# bitfury_m-board-v2_3.net
KiCad netlist of a schematic drawn in EAGLE
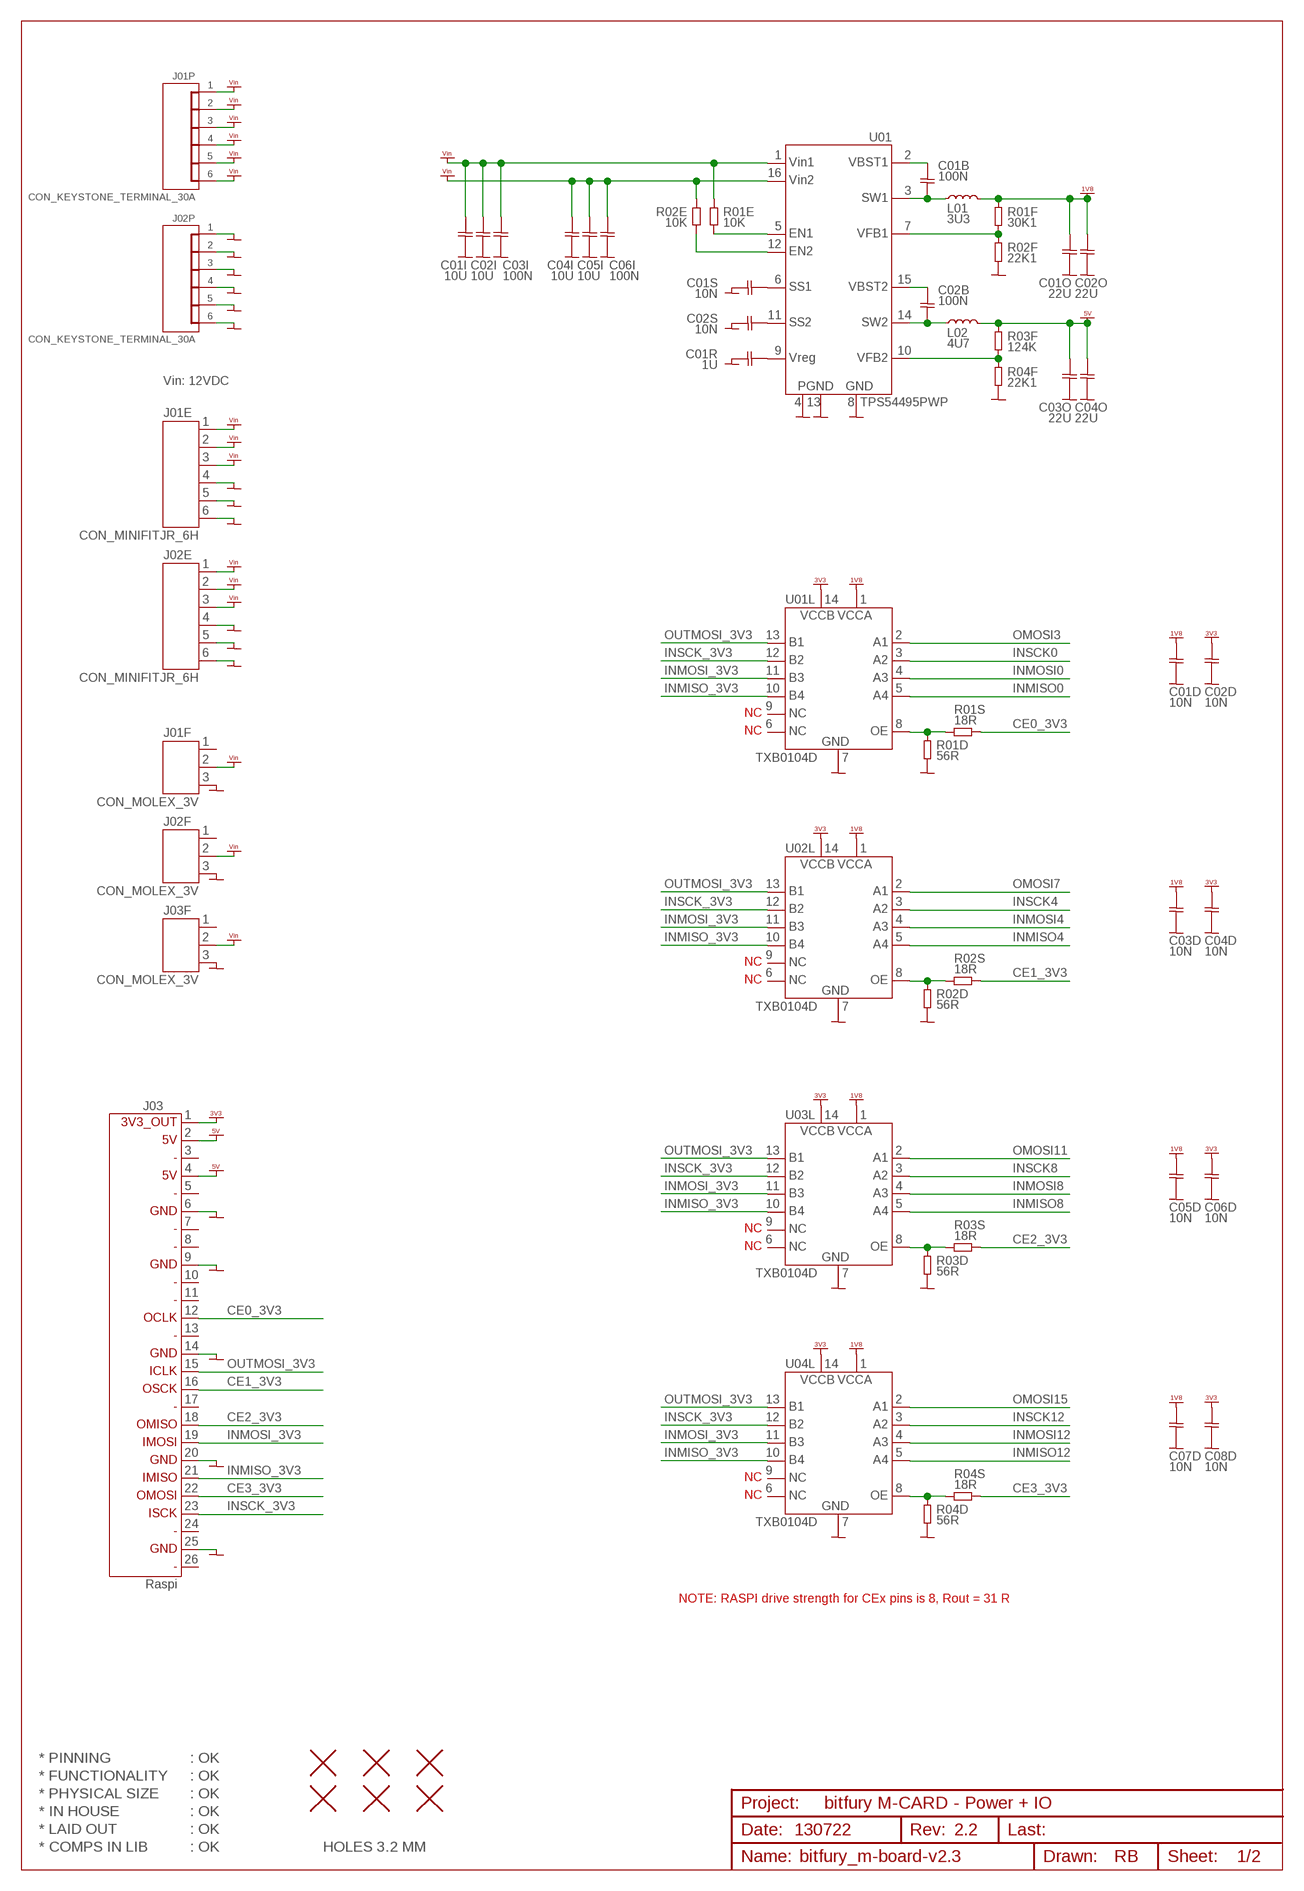
[diagram p0: schematic, sheet 1]
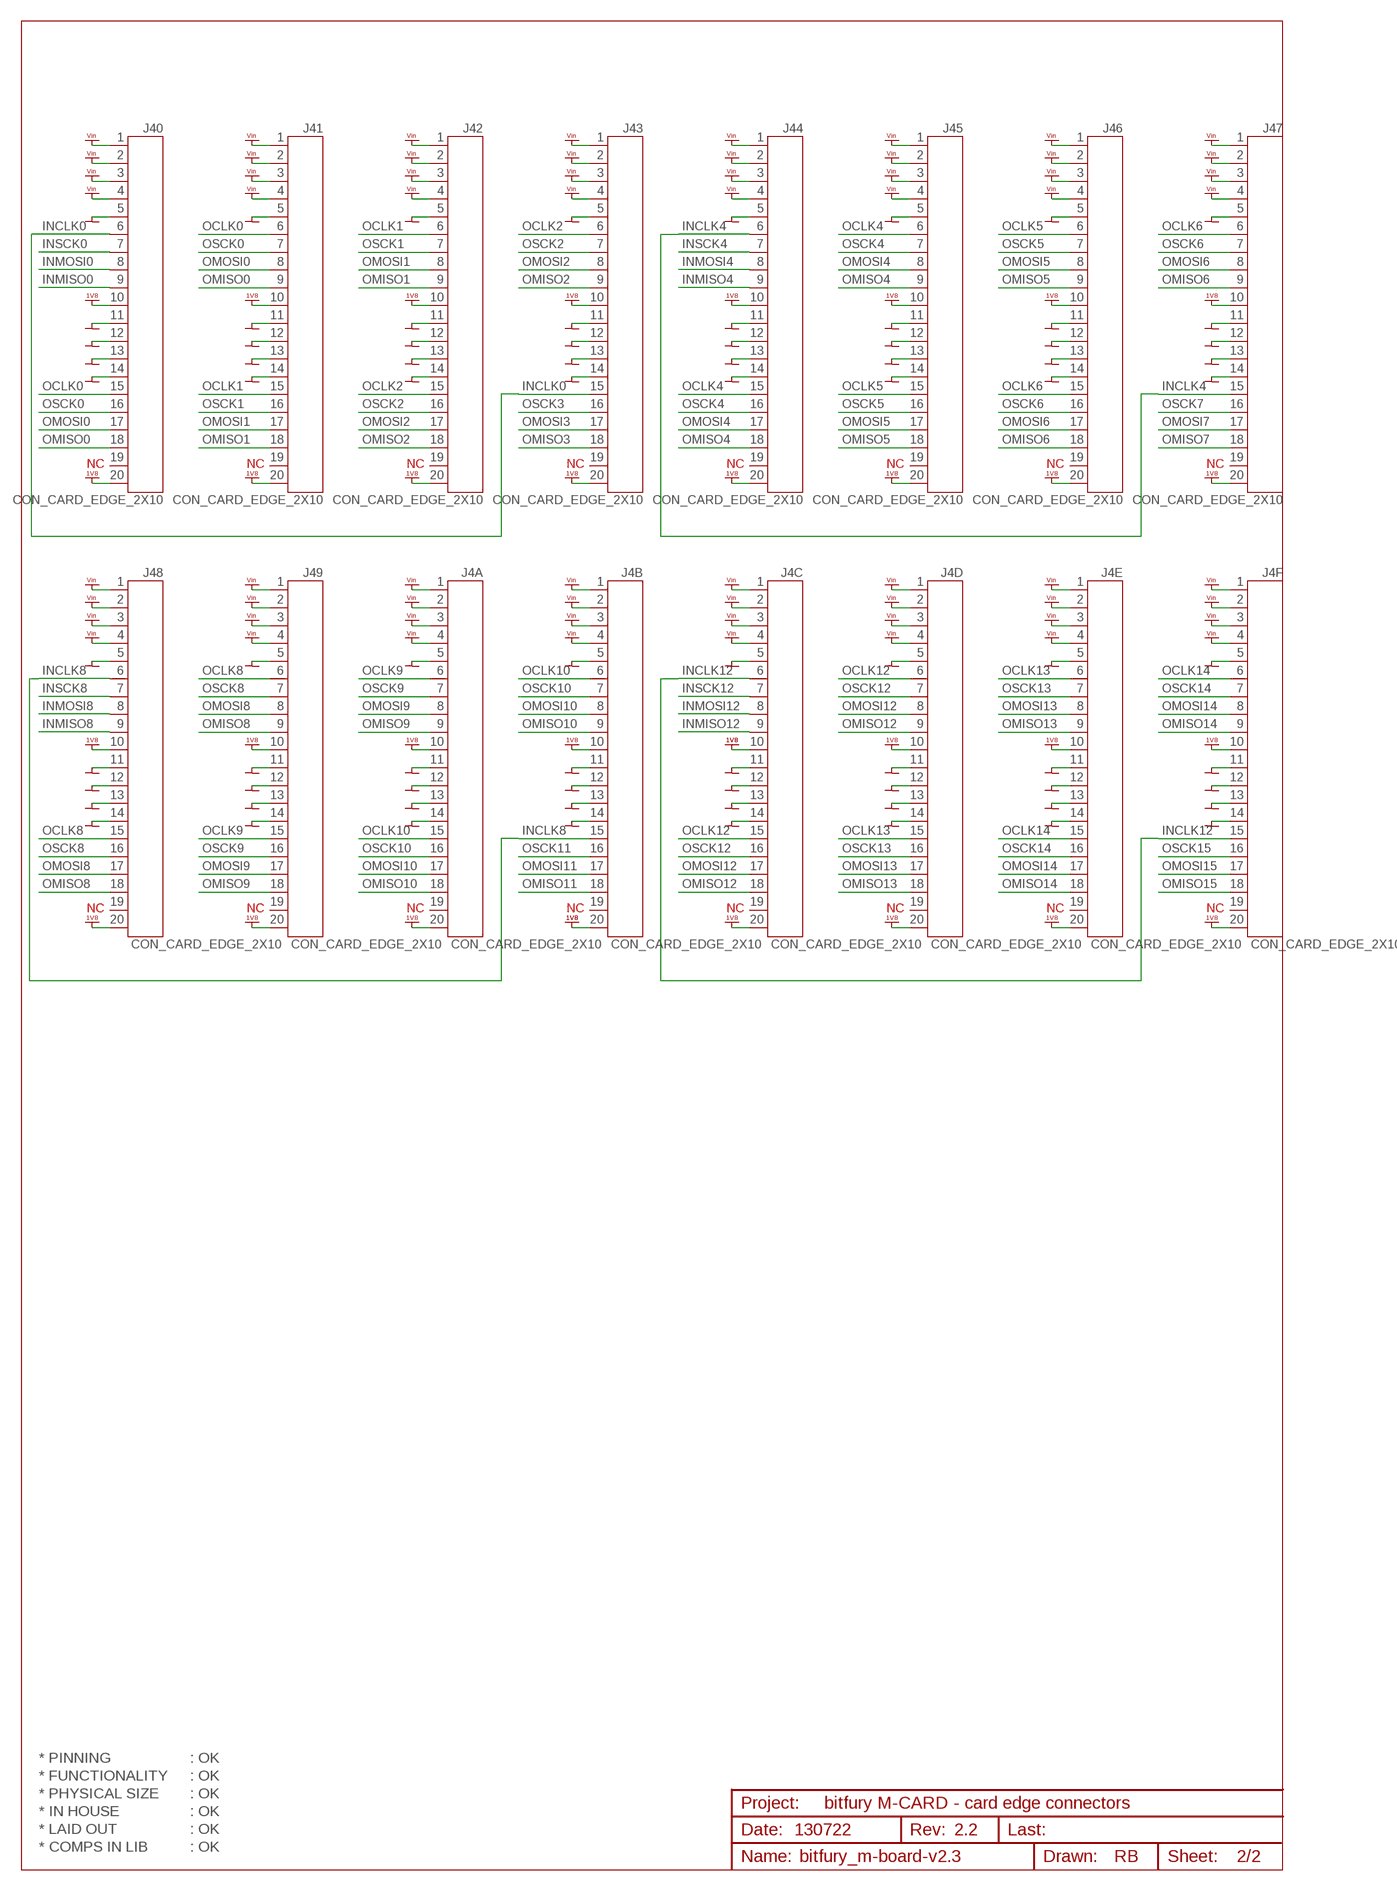
[diagram p1: schematic, sheet 2]

(export (version "E")
  (design (tool "Eeschema 10.0.6"))
  (components
    (comp (ref "C01B")
      (value "100N")
      (footprint "eagle-import:CAP0603")
      (libsource (lib "eagle-import") (part "CAP0603"))
    )
    (comp (ref "C01D")
      (value "10N")
      (footprint "eagle-import:CAP0603")
      (libsource (lib "eagle-import") (part "CAP0603"))
    )
    (comp (ref "C01I")
      (value "10U")
      (footprint "eagle-import:CAP1206")
      (libsource (lib "eagle-import") (part "CAP1206"))
    )
    (comp (ref "C01O")
      (value "22U")
      (footprint "eagle-import:CAP1206")
      (libsource (lib "eagle-import") (part "CAP1206"))
    )
    (comp (ref "C01R")
      (value "1U")
      (footprint "eagle-import:CAP0603")
      (libsource (lib "eagle-import") (part "CAP0603"))
    )
    (comp (ref "C01S")
      (value "10N")
      (footprint "eagle-import:CAP0603")
      (libsource (lib "eagle-import") (part "CAP0603"))
    )
    (comp (ref "C02B")
      (value "100N")
      (footprint "eagle-import:CAP0603")
      (libsource (lib "eagle-import") (part "CAP0603"))
    )
    (comp (ref "C02D")
      (value "10N")
      (footprint "eagle-import:CAP0603")
      (libsource (lib "eagle-import") (part "CAP0603"))
    )
    (comp (ref "C02I")
      (value "10U")
      (footprint "eagle-import:CAP1206")
      (libsource (lib "eagle-import") (part "CAP1206"))
    )
    (comp (ref "C02O")
      (value "22U")
      (footprint "eagle-import:CAP1206")
      (libsource (lib "eagle-import") (part "CAP1206"))
    )
    (comp (ref "C02S")
      (value "10N")
      (footprint "eagle-import:CAP0603")
      (libsource (lib "eagle-import") (part "CAP0603"))
    )
    (comp (ref "C03D")
      (value "10N")
      (footprint "eagle-import:CAP0603")
      (libsource (lib "eagle-import") (part "CAP0603"))
    )
    (comp (ref "C03I")
      (value "100N")
      (footprint "eagle-import:CAP0603")
      (libsource (lib "eagle-import") (part "CAP0603"))
    )
    (comp (ref "C03O")
      (value "22U")
      (footprint "eagle-import:CAP1206")
      (libsource (lib "eagle-import") (part "CAP1206"))
    )
    (comp (ref "C04D")
      (value "10N")
      (footprint "eagle-import:CAP0603")
      (libsource (lib "eagle-import") (part "CAP0603"))
    )
    (comp (ref "C04I")
      (value "10U")
      (footprint "eagle-import:CAP1206")
      (libsource (lib "eagle-import") (part "CAP1206"))
    )
    (comp (ref "C04O")
      (value "22U")
      (footprint "eagle-import:CAP1206")
      (libsource (lib "eagle-import") (part "CAP1206"))
    )
    (comp (ref "C05D")
      (value "10N")
      (footprint "eagle-import:CAP0603")
      (libsource (lib "eagle-import") (part "CAP0603"))
    )
    (comp (ref "C05I")
      (value "10U")
      (footprint "eagle-import:CAP1206")
      (libsource (lib "eagle-import") (part "CAP1206"))
    )
    (comp (ref "C06D")
      (value "10N")
      (footprint "eagle-import:CAP0603")
      (libsource (lib "eagle-import") (part "CAP0603"))
    )
    (comp (ref "C06I")
      (value "100N")
      (footprint "eagle-import:CAP0603")
      (libsource (lib "eagle-import") (part "CAP0603"))
    )
    (comp (ref "C07D")
      (value "10N")
      (footprint "eagle-import:CAP0603")
      (libsource (lib "eagle-import") (part "CAP0603"))
    )
    (comp (ref "C08D")
      (value "10N")
      (footprint "eagle-import:CAP0603")
      (libsource (lib "eagle-import") (part "CAP0603"))
    )
    (comp (ref "H01")
      (value "HOLE_NPTH_3.2MM")
      (footprint "eagle-import:HOLE_NPTH_3.2MM")
      (libsource (lib "eagle-import") (part "HOLE_NPTH_3.2MM"))
    )
    (comp (ref "H02")
      (value "HOLE_NPTH_3.2MM")
      (footprint "eagle-import:HOLE_NPTH_3.2MM")
      (libsource (lib "eagle-import") (part "HOLE_NPTH_3.2MM"))
    )
    (comp (ref "H03")
      (value "HOLE_NPTH_3.2MM")
      (footprint "eagle-import:HOLE_NPTH_3.2MM")
      (libsource (lib "eagle-import") (part "HOLE_NPTH_3.2MM"))
    )
    (comp (ref "H04")
      (value "HOLE_NPTH_3.2MM")
      (footprint "eagle-import:HOLE_NPTH_3.2MM")
      (libsource (lib "eagle-import") (part "HOLE_NPTH_3.2MM"))
    )
    (comp (ref "H05")
      (value "HOLE_NPTH_3.2MM")
      (footprint "eagle-import:HOLE_NPTH_3.2MM")
      (libsource (lib "eagle-import") (part "HOLE_NPTH_3.2MM"))
    )
    (comp (ref "H06")
      (value "HOLE_NPTH_3.2MM")
      (footprint "eagle-import:HOLE_NPTH_3.2MM")
      (libsource (lib "eagle-import") (part "HOLE_NPTH_3.2MM"))
    )
    (comp (ref "J01E")
      (value "CON_MINIFITJR_6H")
      (footprint "eagle-import:CON_MOLEX_MINIFITJR_6H")
      (libsource (lib "eagle-import") (part "CON_MOLEX_MINIFITJR_6H"))
    )
    (comp (ref "J01F")
      (value "CON_MOLEX_3V")
      (footprint "eagle-import:CON_MOLEX_3V")
      (libsource (lib "eagle-import") (part "CON_MOLEX_3V"))
    )
    (comp (ref "J01P")
      (value "CON_KEYSTONE_TERMINAL_30A")
      (footprint "eagle-import:CON_KEYSTONE_TERMINAL_30A")
      (libsource (lib "eagle-import") (part "CON_KEYSTONE_TERMINAL_30A"))
    )
    (comp (ref "J02E")
      (value "CON_MINIFITJR_6H")
      (footprint "eagle-import:CON_MOLEX_MINIFITJR_6H")
      (libsource (lib "eagle-import") (part "CON_MOLEX_MINIFITJR_6H"))
    )
    (comp (ref "J02F")
      (value "CON_MOLEX_3V")
      (footprint "eagle-import:CON_MOLEX_3V")
      (libsource (lib "eagle-import") (part "CON_MOLEX_3V"))
    )
    (comp (ref "J02P")
      (value "CON_KEYSTONE_TERMINAL_30A")
      (footprint "eagle-import:CON_KEYSTONE_TERMINAL_30A")
      (libsource (lib "eagle-import") (part "CON_KEYSTONE_TERMINAL_30A"))
    )
    (comp (ref "J03")
      (value "Raspi")
      (footprint "eagle-import:CON_RASPI_ANGLE")
      (libsource (lib "eagle-import") (part "CON_RASPI_ANGLE"))
    )
    (comp (ref "J03F")
      (value "CON_MOLEX_3V")
      (footprint "eagle-import:CON_MOLEX_3V")
      (libsource (lib "eagle-import") (part "CON_MOLEX_3V"))
    )
    (comp (ref "L01")
      (value "3U3")
      (footprint "eagle-import:L_SPM6530")
      (libsource (lib "eagle-import") (part "L_SPM6530"))
    )
    (comp (ref "L02")
      (value "4U7")
      (footprint "eagle-import:L_SPM6530")
      (libsource (lib "eagle-import") (part "L_SPM6530"))
    )
    (comp (ref "R01D")
      (value "56R")
      (footprint "eagle-import:RES0603")
      (libsource (lib "eagle-import") (part "RES0603"))
    )
    (comp (ref "R01E")
      (value "10K")
      (footprint "eagle-import:RES0603")
      (libsource (lib "eagle-import") (part "RES0603"))
    )
    (comp (ref "R01F")
      (value "30K1")
      (footprint "eagle-import:RES0603")
      (libsource (lib "eagle-import") (part "RES0603"))
    )
    (comp (ref "R01S")
      (value "18R")
      (footprint "eagle-import:RES0603")
      (libsource (lib "eagle-import") (part "RES0603"))
    )
    (comp (ref "R02D")
      (value "56R")
      (footprint "eagle-import:RES0603")
      (libsource (lib "eagle-import") (part "RES0603"))
    )
    (comp (ref "R02E")
      (value "10K")
      (footprint "eagle-import:RES0603")
      (libsource (lib "eagle-import") (part "RES0603"))
    )
    (comp (ref "R02F")
      (value "22K1")
      (footprint "eagle-import:RES0603")
      (libsource (lib "eagle-import") (part "RES0603"))
    )
    (comp (ref "R02S")
      (value "18R")
      (footprint "eagle-import:RES0603")
      (libsource (lib "eagle-import") (part "RES0603"))
    )
    (comp (ref "R03D")
      (value "56R")
      (footprint "eagle-import:RES0603")
      (libsource (lib "eagle-import") (part "RES0603"))
    )
    (comp (ref "R03F")
      (value "124K")
      (footprint "eagle-import:RES0603")
      (libsource (lib "eagle-import") (part "RES0603"))
    )
    (comp (ref "R03S")
      (value "18R")
      (footprint "eagle-import:RES0603")
      (libsource (lib "eagle-import") (part "RES0603"))
    )
    (comp (ref "R04D")
      (value "56R")
      (footprint "eagle-import:RES0603")
      (libsource (lib "eagle-import") (part "RES0603"))
    )
    (comp (ref "R04F")
      (value "22K1")
      (footprint "eagle-import:RES0603")
      (libsource (lib "eagle-import") (part "RES0603"))
    )
    (comp (ref "R04S")
      (value "18R")
      (footprint "eagle-import:RES0603")
      (libsource (lib "eagle-import") (part "RES0603"))
    )
    (comp (ref "U01")
      (value "TPS54495PWP")
      (footprint "eagle-import:HTSSOP16")
      (libsource (lib "eagle-import") (part "TPS54495PWP"))
    )
    (comp (ref "U01L")
      (value "TXB0104D")
      (footprint "eagle-import:SO14")
      (libsource (lib "eagle-import") (part "TXB0104D"))
    )
    (comp (ref "U02L")
      (value "TXB0104D")
      (footprint "eagle-import:SO14")
      (libsource (lib "eagle-import") (part "TXB0104D"))
    )
    (comp (ref "U03L")
      (value "TXB0104D")
      (footprint "eagle-import:SO14")
      (libsource (lib "eagle-import") (part "TXB0104D"))
    )
    (comp (ref "U04L")
      (value "TXB0104D")
      (footprint "eagle-import:SO14")
      (libsource (lib "eagle-import") (part "TXB0104D"))
    )
    (comp (ref "J4A")
      (value "CON_CARD_EDGE_2X10")
      (footprint "eagle-import:CON_CARD_EDGE_2X10")
      (libsource (lib "eagle-import") (part "CON_CARD_EDGE_2X10"))
    )
    (comp (ref "J4B")
      (value "CON_CARD_EDGE_2X10")
      (footprint "eagle-import:CON_CARD_EDGE_2X10")
      (libsource (lib "eagle-import") (part "CON_CARD_EDGE_2X10"))
    )
    (comp (ref "J4C")
      (value "CON_CARD_EDGE_2X10")
      (footprint "eagle-import:CON_CARD_EDGE_2X10")
      (libsource (lib "eagle-import") (part "CON_CARD_EDGE_2X10"))
    )
    (comp (ref "J4D")
      (value "CON_CARD_EDGE_2X10")
      (footprint "eagle-import:CON_CARD_EDGE_2X10")
      (libsource (lib "eagle-import") (part "CON_CARD_EDGE_2X10"))
    )
    (comp (ref "J4E")
      (value "CON_CARD_EDGE_2X10")
      (footprint "eagle-import:CON_CARD_EDGE_2X10")
      (libsource (lib "eagle-import") (part "CON_CARD_EDGE_2X10"))
    )
    (comp (ref "J4F")
      (value "CON_CARD_EDGE_2X10")
      (footprint "eagle-import:CON_CARD_EDGE_2X10")
      (libsource (lib "eagle-import") (part "CON_CARD_EDGE_2X10"))
    )
    (comp (ref "J40")
      (value "CON_CARD_EDGE_2X10")
      (footprint "eagle-import:CON_CARD_EDGE_2X10")
      (libsource (lib "eagle-import") (part "CON_CARD_EDGE_2X10"))
    )
    (comp (ref "J41")
      (value "CON_CARD_EDGE_2X10")
      (footprint "eagle-import:CON_CARD_EDGE_2X10")
      (libsource (lib "eagle-import") (part "CON_CARD_EDGE_2X10"))
    )
    (comp (ref "J42")
      (value "CON_CARD_EDGE_2X10")
      (footprint "eagle-import:CON_CARD_EDGE_2X10")
      (libsource (lib "eagle-import") (part "CON_CARD_EDGE_2X10"))
    )
    (comp (ref "J43")
      (value "CON_CARD_EDGE_2X10")
      (footprint "eagle-import:CON_CARD_EDGE_2X10")
      (libsource (lib "eagle-import") (part "CON_CARD_EDGE_2X10"))
    )
    (comp (ref "J44")
      (value "CON_CARD_EDGE_2X10")
      (footprint "eagle-import:CON_CARD_EDGE_2X10")
      (libsource (lib "eagle-import") (part "CON_CARD_EDGE_2X10"))
    )
    (comp (ref "J45")
      (value "CON_CARD_EDGE_2X10")
      (footprint "eagle-import:CON_CARD_EDGE_2X10")
      (libsource (lib "eagle-import") (part "CON_CARD_EDGE_2X10"))
    )
    (comp (ref "J46")
      (value "CON_CARD_EDGE_2X10")
      (footprint "eagle-import:CON_CARD_EDGE_2X10")
      (libsource (lib "eagle-import") (part "CON_CARD_EDGE_2X10"))
    )
    (comp (ref "J47")
      (value "CON_CARD_EDGE_2X10")
      (footprint "eagle-import:CON_CARD_EDGE_2X10")
      (libsource (lib "eagle-import") (part "CON_CARD_EDGE_2X10"))
    )
    (comp (ref "J48")
      (value "CON_CARD_EDGE_2X10")
      (footprint "eagle-import:CON_CARD_EDGE_2X10")
      (libsource (lib "eagle-import") (part "CON_CARD_EDGE_2X10"))
    )
    (comp (ref "J49")
      (value "CON_CARD_EDGE_2X10")
      (footprint "eagle-import:CON_CARD_EDGE_2X10")
      (libsource (lib "eagle-import") (part "CON_CARD_EDGE_2X10"))
    )
  )
  (nets
    (net (code "1") (name "CE0_3V3") (class "Default")
      (node (ref "J03") (pin "12") (pinfunction "P12_12") (pintype "passive"))
      (node (ref "R01S") (pin "2") (pinfunction "2_2") (pintype "passive"))
    )
    (net (code "2") (name "CE1_3V3") (class "Default")
      (node (ref "J03") (pin "16") (pinfunction "P16_16") (pintype "passive"))
      (node (ref "R02S") (pin "2") (pinfunction "2_2") (pintype "passive"))
    )
    (net (code "3") (name "CE2_3V3") (class "Default")
      (node (ref "J03") (pin "18") (pinfunction "P18_18") (pintype "passive"))
      (node (ref "R03S") (pin "2") (pinfunction "2_2") (pintype "passive"))
    )
    (net (code "4") (name "CE3_3V3") (class "Default")
      (node (ref "J03") (pin "22") (pinfunction "P22_22") (pintype "passive"))
      (node (ref "R04S") (pin "2") (pinfunction "2_2") (pintype "passive"))
    )
    (net (code "5") (name "GND") (class "Default")
      (node (ref "C01D") (pin "2") (pinfunction "2_2") (pintype "passive"))
      (node (ref "C01I") (pin "2") (pinfunction "2_2") (pintype "passive"))
      (node (ref "C01O") (pin "2") (pinfunction "2_2") (pintype "passive"))
      (node (ref "C01R") (pin "1") (pinfunction "1_1") (pintype "passive"))
      (node (ref "C01S") (pin "1") (pinfunction "1_1") (pintype "passive"))
      (node (ref "C02D") (pin "2") (pinfunction "2_2") (pintype "passive"))
      (node (ref "C02I") (pin "2") (pinfunction "2_2") (pintype "passive"))
      (node (ref "C02O") (pin "2") (pinfunction "2_2") (pintype "passive"))
      (node (ref "C02S") (pin "1") (pinfunction "1_1") (pintype "passive"))
      (node (ref "C03D") (pin "2") (pinfunction "2_2") (pintype "passive"))
      (node (ref "C03I") (pin "2") (pinfunction "2_2") (pintype "passive"))
      (node (ref "C03O") (pin "2") (pinfunction "2_2") (pintype "passive"))
      (node (ref "C04D") (pin "2") (pinfunction "2_2") (pintype "passive"))
      (node (ref "C04I") (pin "2") (pinfunction "2_2") (pintype "passive"))
      (node (ref "C04O") (pin "2") (pinfunction "2_2") (pintype "passive"))
      (node (ref "C05D") (pin "2") (pinfunction "2_2") (pintype "passive"))
      (node (ref "C05I") (pin "2") (pinfunction "2_2") (pintype "passive"))
      (node (ref "C06D") (pin "2") (pinfunction "2_2") (pintype "passive"))
      (node (ref "C06I") (pin "2") (pinfunction "2_2") (pintype "passive"))
      (node (ref "C07D") (pin "2") (pinfunction "2_2") (pintype "passive"))
      (node (ref "C08D") (pin "2") (pinfunction "2_2") (pintype "passive"))
      (node (ref "J01E") (pin "4") (pinfunction "4_4") (pintype "passive"))
      (node (ref "J01E") (pin "5") (pinfunction "5_5") (pintype "passive"))
      (node (ref "J01E") (pin "6") (pinfunction "6_6") (pintype "passive"))
      (node (ref "J01F") (pin "3") (pinfunction "3_3") (pintype "passive"))
      (node (ref "J02E") (pin "4") (pinfunction "4_4") (pintype "passive"))
      (node (ref "J02E") (pin "5") (pinfunction "5_5") (pintype "passive"))
      (node (ref "J02E") (pin "6") (pinfunction "6_6") (pintype "passive"))
      (node (ref "J02F") (pin "3") (pinfunction "3_3") (pintype "passive"))
      (node (ref "J02P") (pin "1") (pinfunction "1_1") (pintype "passive"))
      (node (ref "J02P") (pin "2") (pinfunction "2_2") (pintype "passive"))
      (node (ref "J02P") (pin "3") (pinfunction "3_3") (pintype "passive"))
      (node (ref "J02P") (pin "4") (pinfunction "4_4") (pintype "passive"))
      (node (ref "J02P") (pin "5") (pinfunction "5_5") (pintype "passive"))
      (node (ref "J02P") (pin "6") (pinfunction "6_6") (pintype "passive"))
      (node (ref "J03") (pin "14") (pinfunction "P14_14") (pintype "passive"))
      (node (ref "J03") (pin "20") (pinfunction "P20_20") (pintype "passive"))
      (node (ref "J03") (pin "25") (pinfunction "P25_25") (pintype "passive"))
      (node (ref "J03") (pin "6") (pinfunction "P6_6") (pintype "passive"))
      (node (ref "J03") (pin "9") (pinfunction "P9_9") (pintype "passive"))
      (node (ref "J03F") (pin "3") (pinfunction "3_3") (pintype "passive"))
      (node (ref "J40") (pin "11") (pinfunction "11_11") (pintype "passive"))
      (node (ref "J40") (pin "12") (pinfunction "12_12") (pintype "passive"))
      (node (ref "J40") (pin "13") (pinfunction "13_13") (pintype "passive"))
      (node (ref "J40") (pin "14") (pinfunction "14_14") (pintype "passive"))
      (node (ref "J40") (pin "5") (pinfunction "5_5") (pintype "passive"))
      (node (ref "J41") (pin "11") (pinfunction "11_11") (pintype "passive"))
      (node (ref "J41") (pin "12") (pinfunction "12_12") (pintype "passive"))
      (node (ref "J41") (pin "13") (pinfunction "13_13") (pintype "passive"))
      (node (ref "J41") (pin "14") (pinfunction "14_14") (pintype "passive"))
      (node (ref "J41") (pin "5") (pinfunction "5_5") (pintype "passive"))
      (node (ref "J42") (pin "11") (pinfunction "11_11") (pintype "passive"))
      (node (ref "J42") (pin "12") (pinfunction "12_12") (pintype "passive"))
      (node (ref "J42") (pin "13") (pinfunction "13_13") (pintype "passive"))
      (node (ref "J42") (pin "14") (pinfunction "14_14") (pintype "passive"))
      (node (ref "J42") (pin "5") (pinfunction "5_5") (pintype "passive"))
      (node (ref "J43") (pin "11") (pinfunction "11_11") (pintype "passive"))
      (node (ref "J43") (pin "12") (pinfunction "12_12") (pintype "passive"))
      (node (ref "J43") (pin "13") (pinfunction "13_13") (pintype "passive"))
      (node (ref "J43") (pin "14") (pinfunction "14_14") (pintype "passive"))
      (node (ref "J43") (pin "5") (pinfunction "5_5") (pintype "passive"))
      (node (ref "J44") (pin "11") (pinfunction "11_11") (pintype "passive"))
      (node (ref "J44") (pin "12") (pinfunction "12_12") (pintype "passive"))
      (node (ref "J44") (pin "13") (pinfunction "13_13") (pintype "passive"))
      (node (ref "J44") (pin "14") (pinfunction "14_14") (pintype "passive"))
      (node (ref "J44") (pin "5") (pinfunction "5_5") (pintype "passive"))
      (node (ref "J45") (pin "11") (pinfunction "11_11") (pintype "passive"))
      (node (ref "J45") (pin "12") (pinfunction "12_12") (pintype "passive"))
      (node (ref "J45") (pin "13") (pinfunction "13_13") (pintype "passive"))
      (node (ref "J45") (pin "14") (pinfunction "14_14") (pintype "passive"))
      (node (ref "J45") (pin "5") (pinfunction "5_5") (pintype "passive"))
      (node (ref "J46") (pin "11") (pinfunction "11_11") (pintype "passive"))
      (node (ref "J46") (pin "12") (pinfunction "12_12") (pintype "passive"))
      (node (ref "J46") (pin "13") (pinfunction "13_13") (pintype "passive"))
      (node (ref "J46") (pin "14") (pinfunction "14_14") (pintype "passive"))
      (node (ref "J46") (pin "5") (pinfunction "5_5") (pintype "passive"))
      (node (ref "J47") (pin "11") (pinfunction "11_11") (pintype "passive"))
      (node (ref "J47") (pin "12") (pinfunction "12_12") (pintype "passive"))
      (node (ref "J47") (pin "13") (pinfunction "13_13") (pintype "passive"))
      (node (ref "J47") (pin "14") (pinfunction "14_14") (pintype "passive"))
      (node (ref "J47") (pin "5") (pinfunction "5_5") (pintype "passive"))
      (node (ref "J48") (pin "11") (pinfunction "11_11") (pintype "passive"))
      (node (ref "J48") (pin "12") (pinfunction "12_12") (pintype "passive"))
      (node (ref "J48") (pin "13") (pinfunction "13_13") (pintype "passive"))
      (node (ref "J48") (pin "14") (pinfunction "14_14") (pintype "passive"))
      (node (ref "J48") (pin "5") (pinfunction "5_5") (pintype "passive"))
      (node (ref "J49") (pin "11") (pinfunction "11_11") (pintype "passive"))
      (node (ref "J49") (pin "12") (pinfunction "12_12") (pintype "passive"))
      (node (ref "J49") (pin "13") (pinfunction "13_13") (pintype "passive"))
      (node (ref "J49") (pin "14") (pinfunction "14_14") (pintype "passive"))
      (node (ref "J49") (pin "5") (pinfunction "5_5") (pintype "passive"))
      (node (ref "J4A") (pin "11") (pinfunction "11_11") (pintype "passive"))
      (node (ref "J4A") (pin "12") (pinfunction "12_12") (pintype "passive"))
      (node (ref "J4A") (pin "13") (pinfunction "13_13") (pintype "passive"))
      (node (ref "J4A") (pin "14") (pinfunction "14_14") (pintype "passive"))
      (node (ref "J4A") (pin "5") (pinfunction "5_5") (pintype "passive"))
      (node (ref "J4B") (pin "11") (pinfunction "11_11") (pintype "passive"))
      (node (ref "J4B") (pin "12") (pinfunction "12_12") (pintype "passive"))
      (node (ref "J4B") (pin "13") (pinfunction "13_13") (pintype "passive"))
      (node (ref "J4B") (pin "14") (pinfunction "14_14") (pintype "passive"))
      (node (ref "J4B") (pin "5") (pinfunction "5_5") (pintype "passive"))
      (node (ref "J4C") (pin "11") (pinfunction "11_11") (pintype "passive"))
      (node (ref "J4C") (pin "12") (pinfunction "12_12") (pintype "passive"))
      (node (ref "J4C") (pin "13") (pinfunction "13_13") (pintype "passive"))
      (node (ref "J4C") (pin "14") (pinfunction "14_14") (pintype "passive"))
      (node (ref "J4C") (pin "5") (pinfunction "5_5") (pintype "passive"))
      (node (ref "J4D") (pin "11") (pinfunction "11_11") (pintype "passive"))
      (node (ref "J4D") (pin "12") (pinfunction "12_12") (pintype "passive"))
      (node (ref "J4D") (pin "13") (pinfunction "13_13") (pintype "passive"))
      (node (ref "J4D") (pin "14") (pinfunction "14_14") (pintype "passive"))
      (node (ref "J4D") (pin "5") (pinfunction "5_5") (pintype "passive"))
      (node (ref "J4E") (pin "11") (pinfunction "11_11") (pintype "passive"))
      (node (ref "J4E") (pin "12") (pinfunction "12_12") (pintype "passive"))
      (node (ref "J4E") (pin "13") (pinfunction "13_13") (pintype "passive"))
      (node (ref "J4E") (pin "14") (pinfunction "14_14") (pintype "passive"))
      (node (ref "J4E") (pin "5") (pinfunction "5_5") (pintype "passive"))
      (node (ref "J4F") (pin "11") (pinfunction "11_11") (pintype "passive"))
      (node (ref "J4F") (pin "12") (pinfunction "12_12") (pintype "passive"))
      (node (ref "J4F") (pin "13") (pinfunction "13_13") (pintype "passive"))
      (node (ref "J4F") (pin "14") (pinfunction "14_14") (pintype "passive"))
      (node (ref "J4F") (pin "5") (pinfunction "5_5") (pintype "passive"))
      (node (ref "R01D") (pin "2") (pinfunction "2_2") (pintype "passive"))
      (node (ref "R02D") (pin "2") (pinfunction "2_2") (pintype "passive"))
      (node (ref "R02F") (pin "2") (pinfunction "2_2") (pintype "passive"))
      (node (ref "R03D") (pin "2") (pinfunction "2_2") (pintype "passive"))
      (node (ref "R04D") (pin "2") (pinfunction "2_2") (pintype "passive"))
      (node (ref "R04F") (pin "2") (pinfunction "2_2") (pintype "passive"))
      (node (ref "U01") (pin "13") (pinfunction "13.PGND_13") (pintype "passive"))
      (node (ref "U01") (pin "4") (pinfunction "4.PGND_4") (pintype "passive"))
      (node (ref "U01") (pin "8") (pinfunction "8.GND_8") (pintype "passive"))
      (node (ref "U01") (pin "EP") (pinfunction "13.PGND_EP") (pintype "passive"))
      (node (ref "U01") (pin "P1") (pinfunction "13.PGND_P1") (pintype "passive"))
      (node (ref "U01") (pin "P2") (pinfunction "13.PGND_P2") (pintype "passive"))
      (node (ref "U01") (pin "P3") (pinfunction "13.PGND_P3") (pintype "passive"))
      (node (ref "U01") (pin "P4") (pinfunction "13.PGND_P4") (pintype "passive"))
      (node (ref "U01") (pin "P5") (pinfunction "13.PGND_P5") (pintype "passive"))
      (node (ref "U01") (pin "P6") (pinfunction "13.PGND_P6") (pintype "passive"))
      (node (ref "U01L") (pin "7") (pinfunction "7.GND_7") (pintype "passive"))
      (node (ref "U02L") (pin "7") (pinfunction "7.GND_7") (pintype "passive"))
      (node (ref "U03L") (pin "7") (pinfunction "7.GND_7") (pintype "passive"))
      (node (ref "U04L") (pin "7") (pinfunction "7.GND_7") (pintype "passive"))
    )
    (net (code "6") (name "INCLK0") (class "Default")
      (node (ref "J40") (pin "6") (pinfunction "6_6") (pintype "passive"))
      (node (ref "J43") (pin "15") (pinfunction "15_15") (pintype "passive"))
    )
    (net (code "7") (name "INCLK4") (class "Default")
      (node (ref "J44") (pin "6") (pinfunction "6_6") (pintype "passive"))
      (node (ref "J47") (pin "15") (pinfunction "15_15") (pintype "passive"))
    )
    (net (code "8") (name "INCLK8") (class "Default")
      (node (ref "J48") (pin "6") (pinfunction "6_6") (pintype "passive"))
      (node (ref "J4B") (pin "15") (pinfunction "15_15") (pintype "passive"))
    )
    (net (code "9") (name "INCLK12") (class "Default")
      (node (ref "J4C") (pin "6") (pinfunction "6_6") (pintype "passive"))
      (node (ref "J4F") (pin "15") (pinfunction "15_15") (pintype "passive"))
    )
    (net (code "10") (name "INMISO0") (class "Default")
      (node (ref "J40") (pin "9") (pinfunction "9_9") (pintype "passive"))
      (node (ref "U01L") (pin "5") (pinfunction "5.A4_5") (pintype "passive"))
    )
    (net (code "11") (name "INMISO4") (class "Default")
      (node (ref "J44") (pin "9") (pinfunction "9_9") (pintype "passive"))
      (node (ref "U02L") (pin "5") (pinfunction "5.A4_5") (pintype "passive"))
    )
    (net (code "12") (name "INMISO8") (class "Default")
      (node (ref "J48") (pin "9") (pinfunction "9_9") (pintype "passive"))
      (node (ref "U03L") (pin "5") (pinfunction "5.A4_5") (pintype "passive"))
    )
    (net (code "13") (name "INMISO12") (class "Default")
      (node (ref "J4C") (pin "9") (pinfunction "9_9") (pintype "passive"))
      (node (ref "U04L") (pin "5") (pinfunction "5.A4_5") (pintype "passive"))
    )
    (net (code "14") (name "INMISO_3V3") (class "Default")
      (node (ref "J03") (pin "21") (pinfunction "P21_21") (pintype "passive"))
      (node (ref "U01L") (pin "10") (pinfunction "10.B4_10") (pintype "passive"))
      (node (ref "U02L") (pin "10") (pinfunction "10.B4_10") (pintype "passive"))
      (node (ref "U03L") (pin "10") (pinfunction "10.B4_10") (pintype "passive"))
      (node (ref "U04L") (pin "10") (pinfunction "10.B4_10") (pintype "passive"))
    )
    (net (code "15") (name "INMOSI0") (class "Default")
      (node (ref "J40") (pin "8") (pinfunction "8_8") (pintype "passive"))
      (node (ref "U01L") (pin "4") (pinfunction "4.A3_4") (pintype "passive"))
    )
    (net (code "16") (name "INMOSI4") (class "Default")
      (node (ref "J44") (pin "8") (pinfunction "8_8") (pintype "passive"))
      (node (ref "U02L") (pin "4") (pinfunction "4.A3_4") (pintype "passive"))
    )
    (net (code "17") (name "INMOSI8") (class "Default")
      (node (ref "J48") (pin "8") (pinfunction "8_8") (pintype "passive"))
      (node (ref "U03L") (pin "4") (pinfunction "4.A3_4") (pintype "passive"))
    )
    (net (code "18") (name "INMOSI12") (class "Default")
      (node (ref "J4C") (pin "8") (pinfunction "8_8") (pintype "passive"))
      (node (ref "U04L") (pin "4") (pinfunction "4.A3_4") (pintype "passive"))
    )
    (net (code "19") (name "INMOSI_3V3") (class "Default")
      (node (ref "J03") (pin "19") (pinfunction "P19_19") (pintype "passive"))
      (node (ref "U01L") (pin "11") (pinfunction "11.B3_11") (pintype "passive"))
      (node (ref "U02L") (pin "11") (pinfunction "11.B3_11") (pintype "passive"))
      (node (ref "U03L") (pin "11") (pinfunction "11.B3_11") (pintype "passive"))
      (node (ref "U04L") (pin "11") (pinfunction "11.B3_11") (pintype "passive"))
    )
    (net (code "20") (name "INSCK0") (class "Default")
      (node (ref "J40") (pin "7") (pinfunction "7_7") (pintype "passive"))
      (node (ref "U01L") (pin "3") (pinfunction "3.A2_3") (pintype "passive"))
    )
    (net (code "21") (name "INSCK4") (class "Default")
      (node (ref "J44") (pin "7") (pinfunction "7_7") (pintype "passive"))
      (node (ref "U02L") (pin "3") (pinfunction "3.A2_3") (pintype "passive"))
    )
    (net (code "22") (name "INSCK8") (class "Default")
      (node (ref "J48") (pin "7") (pinfunction "7_7") (pintype "passive"))
      (node (ref "U03L") (pin "3") (pinfunction "3.A2_3") (pintype "passive"))
    )
    (net (code "23") (name "INSCK12") (class "Default")
      (node (ref "J4C") (pin "7") (pinfunction "7_7") (pintype "passive"))
      (node (ref "U04L") (pin "3") (pinfunction "3.A2_3") (pintype "passive"))
    )
    (net (code "24") (name "INSCK_3V3") (class "Default")
      (node (ref "J03") (pin "23") (pinfunction "P23_23") (pintype "passive"))
      (node (ref "U01L") (pin "12") (pinfunction "12.B2_12") (pintype "passive"))
      (node (ref "U02L") (pin "12") (pinfunction "12.B2_12") (pintype "passive"))
      (node (ref "U03L") (pin "12") (pinfunction "12.B2_12") (pintype "passive"))
      (node (ref "U04L") (pin "12") (pinfunction "12.B2_12") (pintype "passive"))
    )
    (net (code "25") (name "Net-(U01-2.VBST1)") (class "Default")
      (node (ref "C01B") (pin "1") (pinfunction "1_1") (pintype "passive"))
      (node (ref "U01") (pin "2") (pinfunction "2.VBST1_2") (pintype "passive"))
    )
    (net (code "26") (name "Net-(U01-3.SW1)") (class "Default")
      (node (ref "C01B") (pin "2") (pinfunction "2_2") (pintype "passive"))
      (node (ref "L01") (pin "1") (pinfunction "1_1") (pintype "passive"))
      (node (ref "U01") (pin "3") (pinfunction "3.SW1_3") (pintype "passive"))
    )
    (net (code "27") (name "Net-(U01-5.EN1)") (class "Default")
      (node (ref "R01E") (pin "2") (pinfunction "2_2") (pintype "passive"))
      (node (ref "U01") (pin "5") (pinfunction "5.EN1_5") (pintype "passive"))
    )
    (net (code "28") (name "Net-(U01-6.SS1)") (class "Default")
      (node (ref "C01S") (pin "2") (pinfunction "2_2") (pintype "passive"))
      (node (ref "U01") (pin "6") (pinfunction "6.SS1_6") (pintype "passive"))
    )
    (net (code "29") (name "Net-(U01-7.VFB1)") (class "Default")
      (node (ref "R01F") (pin "2") (pinfunction "2_2") (pintype "passive"))
      (node (ref "R02F") (pin "1") (pinfunction "1_1") (pintype "passive"))
      (node (ref "U01") (pin "7") (pinfunction "7.VFB1_7") (pintype "passive"))
    )
    (net (code "30") (name "Net-(U01-9.VREG)") (class "Default")
      (node (ref "C01R") (pin "2") (pinfunction "2_2") (pintype "passive"))
      (node (ref "U01") (pin "9") (pinfunction "9.VREG_9") (pintype "passive"))
    )
    (net (code "31") (name "Net-(U01-10.VFB2)") (class "Default")
      (node (ref "R03F") (pin "2") (pinfunction "2_2") (pintype "passive"))
      (node (ref "R04F") (pin "1") (pinfunction "1_1") (pintype "passive"))
      (node (ref "U01") (pin "10") (pinfunction "10.VFB2_10") (pintype "passive"))
    )
    (net (code "32") (name "Net-(U01-11.SS2)") (class "Default")
      (node (ref "C02S") (pin "2") (pinfunction "2_2") (pintype "passive"))
      (node (ref "U01") (pin "11") (pinfunction "11.SS2_11") (pintype "passive"))
    )
    (net (code "33") (name "Net-(U01-12.EN2)") (class "Default")
      (node (ref "R02E") (pin "2") (pinfunction "2_2") (pintype "passive"))
      (node (ref "U01") (pin "12") (pinfunction "12.EN2_12") (pintype "passive"))
    )
    (net (code "34") (name "Net-(U01-14.SW2)") (class "Default")
      (node (ref "C02B") (pin "2") (pinfunction "2_2") (pintype "passive"))
      (node (ref "L02") (pin "1") (pinfunction "1_1") (pintype "passive"))
      (node (ref "U01") (pin "14") (pinfunction "14.SW2_14") (pintype "passive"))
    )
    (net (code "35") (name "Net-(U01-15.VBST2)") (class "Default")
      (node (ref "C02B") (pin "1") (pinfunction "1_1") (pintype "passive"))
      (node (ref "U01") (pin "15") (pinfunction "15.VBST2_15") (pintype "passive"))
    )
    (net (code "36") (name "Net-(U01L-8.OE)") (class "Default")
      (node (ref "R01D") (pin "1") (pinfunction "1_1") (pintype "passive"))
      (node (ref "R01S") (pin "1") (pinfunction "1_1") (pintype "passive"))
      (node (ref "U01L") (pin "8") (pinfunction "8.OE_8") (pintype "passive"))
    )
    (net (code "37") (name "Net-(U02L-8.OE)") (class "Default")
      (node (ref "R02D") (pin "1") (pinfunction "1_1") (pintype "passive"))
      (node (ref "R02S") (pin "1") (pinfunction "1_1") (pintype "passive"))
      (node (ref "U02L") (pin "8") (pinfunction "8.OE_8") (pintype "passive"))
    )
    (net (code "38") (name "Net-(U03L-8.OE)") (class "Default")
      (node (ref "R03D") (pin "1") (pinfunction "1_1") (pintype "passive"))
      (node (ref "R03S") (pin "1") (pinfunction "1_1") (pintype "passive"))
      (node (ref "U03L") (pin "8") (pinfunction "8.OE_8") (pintype "passive"))
    )
    (net (code "39") (name "Net-(U04L-8.OE)") (class "Default")
      (node (ref "R04D") (pin "1") (pinfunction "1_1") (pintype "passive"))
      (node (ref "R04S") (pin "1") (pinfunction "1_1") (pintype "passive"))
      (node (ref "U04L") (pin "8") (pinfunction "8.OE_8") (pintype "passive"))
    )
    (net (code "40") (name "OCLK0") (class "Default")
      (node (ref "J40") (pin "15") (pinfunction "15_15") (pintype "passive"))
      (node (ref "J41") (pin "6") (pinfunction "6_6") (pintype "passive"))
    )
    (net (code "41") (name "OCLK1") (class "Default")
      (node (ref "J41") (pin "15") (pinfunction "15_15") (pintype "passive"))
      (node (ref "J42") (pin "6") (pinfunction "6_6") (pintype "passive"))
    )
    (net (code "42") (name "OCLK2") (class "Default")
      (node (ref "J42") (pin "15") (pinfunction "15_15") (pintype "passive"))
      (node (ref "J43") (pin "6") (pinfunction "6_6") (pintype "passive"))
    )
    (net (code "43") (name "OCLK4") (class "Default")
      (node (ref "J44") (pin "15") (pinfunction "15_15") (pintype "passive"))
      (node (ref "J45") (pin "6") (pinfunction "6_6") (pintype "passive"))
    )
    (net (code "44") (name "OCLK5") (class "Default")
      (node (ref "J45") (pin "15") (pinfunction "15_15") (pintype "passive"))
      (node (ref "J46") (pin "6") (pinfunction "6_6") (pintype "passive"))
    )
    (net (code "45") (name "OCLK6") (class "Default")
      (node (ref "J46") (pin "15") (pinfunction "15_15") (pintype "passive"))
      (node (ref "J47") (pin "6") (pinfunction "6_6") (pintype "passive"))
    )
    (net (code "46") (name "OCLK8") (class "Default")
      (node (ref "J48") (pin "15") (pinfunction "15_15") (pintype "passive"))
      (node (ref "J49") (pin "6") (pinfunction "6_6") (pintype "passive"))
    )
    (net (code "47") (name "OCLK9") (class "Default")
      (node (ref "J49") (pin "15") (pinfunction "15_15") (pintype "passive"))
      (node (ref "J4A") (pin "6") (pinfunction "6_6") (pintype "passive"))
    )
    (net (code "48") (name "OCLK10") (class "Default")
      (node (ref "J4A") (pin "15") (pinfunction "15_15") (pintype "passive"))
      (node (ref "J4B") (pin "6") (pinfunction "6_6") (pintype "passive"))
    )
    (net (code "49") (name "OCLK12") (class "Default")
      (node (ref "J4C") (pin "15") (pinfunction "15_15") (pintype "passive"))
      (node (ref "J4D") (pin "6") (pinfunction "6_6") (pintype "passive"))
    )
    (net (code "50") (name "OCLK13") (class "Default")
      (node (ref "J4D") (pin "15") (pinfunction "15_15") (pintype "passive"))
      (node (ref "J4E") (pin "6") (pinfunction "6_6") (pintype "passive"))
    )
    (net (code "51") (name "OCLK14") (class "Default")
      (node (ref "J4E") (pin "15") (pinfunction "15_15") (pintype "passive"))
      (node (ref "J4F") (pin "6") (pinfunction "6_6") (pintype "passive"))
    )
    (net (code "52") (name "OMISO0") (class "Default")
      (node (ref "J40") (pin "18") (pinfunction "18_18") (pintype "passive"))
      (node (ref "J41") (pin "9") (pinfunction "9_9") (pintype "passive"))
    )
    (net (code "53") (name "OMISO1") (class "Default")
      (node (ref "J41") (pin "18") (pinfunction "18_18") (pintype "passive"))
      (node (ref "J42") (pin "9") (pinfunction "9_9") (pintype "passive"))
    )
    (net (code "54") (name "OMISO2") (class "Default")
      (node (ref "J42") (pin "18") (pinfunction "18_18") (pintype "passive"))
      (node (ref "J43") (pin "9") (pinfunction "9_9") (pintype "passive"))
    )
    (net (code "55") (name "OMISO3") (class "Default")
      (node (ref "J43") (pin "18") (pinfunction "18_18") (pintype "passive"))
    )
    (net (code "56") (name "OMISO4") (class "Default")
      (node (ref "J44") (pin "18") (pinfunction "18_18") (pintype "passive"))
      (node (ref "J45") (pin "9") (pinfunction "9_9") (pintype "passive"))
    )
    (net (code "57") (name "OMISO5") (class "Default")
      (node (ref "J45") (pin "18") (pinfunction "18_18") (pintype "passive"))
      (node (ref "J46") (pin "9") (pinfunction "9_9") (pintype "passive"))
    )
    (net (code "58") (name "OMISO6") (class "Default")
      (node (ref "J46") (pin "18") (pinfunction "18_18") (pintype "passive"))
      (node (ref "J47") (pin "9") (pinfunction "9_9") (pintype "passive"))
    )
    (net (code "59") (name "OMISO7") (class "Default")
      (node (ref "J47") (pin "18") (pinfunction "18_18") (pintype "passive"))
    )
    (net (code "60") (name "OMISO8") (class "Default")
      (node (ref "J48") (pin "18") (pinfunction "18_18") (pintype "passive"))
      (node (ref "J49") (pin "9") (pinfunction "9_9") (pintype "passive"))
    )
    (net (code "61") (name "OMISO9") (class "Default")
      (node (ref "J49") (pin "18") (pinfunction "18_18") (pintype "passive"))
      (node (ref "J4A") (pin "9") (pinfunction "9_9") (pintype "passive"))
    )
    (net (code "62") (name "OMISO10") (class "Default")
      (node (ref "J4A") (pin "18") (pinfunction "18_18") (pintype "passive"))
      (node (ref "J4B") (pin "9") (pinfunction "9_9") (pintype "passive"))
    )
    (net (code "63") (name "OMISO11") (class "Default")
      (node (ref "J4B") (pin "18") (pinfunction "18_18") (pintype "passive"))
    )
    (net (code "64") (name "OMISO12") (class "Default")
      (node (ref "J4C") (pin "18") (pinfunction "18_18") (pintype "passive"))
      (node (ref "J4D") (pin "9") (pinfunction "9_9") (pintype "passive"))
    )
    (net (code "65") (name "OMISO13") (class "Default")
      (node (ref "J4D") (pin "18") (pinfunction "18_18") (pintype "passive"))
      (node (ref "J4E") (pin "9") (pinfunction "9_9") (pintype "passive"))
    )
    (net (code "66") (name "OMISO14") (class "Default")
      (node (ref "J4E") (pin "18") (pinfunction "18_18") (pintype "passive"))
      (node (ref "J4F") (pin "9") (pinfunction "9_9") (pintype "passive"))
    )
    (net (code "67") (name "OMISO15") (class "Default")
      (node (ref "J4F") (pin "18") (pinfunction "18_18") (pintype "passive"))
    )
    (net (code "68") (name "OMOSI0") (class "Default")
      (node (ref "J40") (pin "17") (pinfunction "17_17") (pintype "passive"))
      (node (ref "J41") (pin "8") (pinfunction "8_8") (pintype "passive"))
    )
    (net (code "69") (name "OMOSI1") (class "Default")
      (node (ref "J41") (pin "17") (pinfunction "17_17") (pintype "passive"))
      (node (ref "J42") (pin "8") (pinfunction "8_8") (pintype "passive"))
    )
    (net (code "70") (name "OMOSI2") (class "Default")
      (node (ref "J42") (pin "17") (pinfunction "17_17") (pintype "passive"))
      (node (ref "J43") (pin "8") (pinfunction "8_8") (pintype "passive"))
    )
    (net (code "71") (name "OMOSI3") (class "Default")
      (node (ref "J43") (pin "17") (pinfunction "17_17") (pintype "passive"))
      (node (ref "U01L") (pin "2") (pinfunction "2.A1_2") (pintype "passive"))
    )
    (net (code "72") (name "OMOSI4") (class "Default")
      (node (ref "J44") (pin "17") (pinfunction "17_17") (pintype "passive"))
      (node (ref "J45") (pin "8") (pinfunction "8_8") (pintype "passive"))
    )
    (net (code "73") (name "OMOSI5") (class "Default")
      (node (ref "J45") (pin "17") (pinfunction "17_17") (pintype "passive"))
      (node (ref "J46") (pin "8") (pinfunction "8_8") (pintype "passive"))
    )
    (net (code "74") (name "OMOSI6") (class "Default")
      (node (ref "J46") (pin "17") (pinfunction "17_17") (pintype "passive"))
      (node (ref "J47") (pin "8") (pinfunction "8_8") (pintype "passive"))
    )
    (net (code "75") (name "OMOSI7") (class "Default")
      (node (ref "J47") (pin "17") (pinfunction "17_17") (pintype "passive"))
      (node (ref "U02L") (pin "2") (pinfunction "2.A1_2") (pintype "passive"))
    )
    (net (code "76") (name "OMOSI8") (class "Default")
      (node (ref "J48") (pin "17") (pinfunction "17_17") (pintype "passive"))
      (node (ref "J49") (pin "8") (pinfunction "8_8") (pintype "passive"))
    )
    (net (code "77") (name "OMOSI9") (class "Default")
      (node (ref "J49") (pin "17") (pinfunction "17_17") (pintype "passive"))
      (node (ref "J4A") (pin "8") (pinfunction "8_8") (pintype "passive"))
    )
    (net (code "78") (name "OMOSI10") (class "Default")
      (node (ref "J4A") (pin "17") (pinfunction "17_17") (pintype "passive"))
      (node (ref "J4B") (pin "8") (pinfunction "8_8") (pintype "passive"))
    )
    (net (code "79") (name "OMOSI11") (class "Default")
      (node (ref "J4B") (pin "17") (pinfunction "17_17") (pintype "passive"))
      (node (ref "U03L") (pin "2") (pinfunction "2.A1_2") (pintype "passive"))
    )
    (net (code "80") (name "OMOSI12") (class "Default")
      (node (ref "J4C") (pin "17") (pinfunction "17_17") (pintype "passive"))
      (node (ref "J4D") (pin "8") (pinfunction "8_8") (pintype "passive"))
    )
    (net (code "81") (name "OMOSI13") (class "Default")
      (node (ref "J4D") (pin "17") (pinfunction "17_17") (pintype "passive"))
      (node (ref "J4E") (pin "8") (pinfunction "8_8") (pintype "passive"))
    )
    (net (code "82") (name "OMOSI14") (class "Default")
      (node (ref "J4E") (pin "17") (pinfunction "17_17") (pintype "passive"))
      (node (ref "J4F") (pin "8") (pinfunction "8_8") (pintype "passive"))
    )
    (net (code "83") (name "OMOSI15") (class "Default")
      (node (ref "J4F") (pin "17") (pinfunction "17_17") (pintype "passive"))
      (node (ref "U04L") (pin "2") (pinfunction "2.A1_2") (pintype "passive"))
    )
    (net (code "84") (name "OSCK0") (class "Default")
      (node (ref "J40") (pin "16") (pinfunction "16_16") (pintype "passive"))
      (node (ref "J41") (pin "7") (pinfunction "7_7") (pintype "passive"))
    )
    (net (code "85") (name "OSCK1") (class "Default")
      (node (ref "J41") (pin "16") (pinfunction "16_16") (pintype "passive"))
      (node (ref "J42") (pin "7") (pinfunction "7_7") (pintype "passive"))
    )
    (net (code "86") (name "OSCK2") (class "Default")
      (node (ref "J42") (pin "16") (pinfunction "16_16") (pintype "passive"))
      (node (ref "J43") (pin "7") (pinfunction "7_7") (pintype "passive"))
    )
    (net (code "87") (name "OSCK3") (class "Default")
      (node (ref "J43") (pin "16") (pinfunction "16_16") (pintype "passive"))
    )
    (net (code "88") (name "OSCK4") (class "Default")
      (node (ref "J44") (pin "16") (pinfunction "16_16") (pintype "passive"))
      (node (ref "J45") (pin "7") (pinfunction "7_7") (pintype "passive"))
    )
    (net (code "89") (name "OSCK5") (class "Default")
      (node (ref "J45") (pin "16") (pinfunction "16_16") (pintype "passive"))
      (node (ref "J46") (pin "7") (pinfunction "7_7") (pintype "passive"))
    )
    (net (code "90") (name "OSCK6") (class "Default")
      (node (ref "J46") (pin "16") (pinfunction "16_16") (pintype "passive"))
      (node (ref "J47") (pin "7") (pinfunction "7_7") (pintype "passive"))
    )
    (net (code "91") (name "OSCK7") (class "Default")
      (node (ref "J47") (pin "16") (pinfunction "16_16") (pintype "passive"))
    )
    (net (code "92") (name "OSCK8") (class "Default")
      (node (ref "J48") (pin "16") (pinfunction "16_16") (pintype "passive"))
      (node (ref "J49") (pin "7") (pinfunction "7_7") (pintype "passive"))
    )
    (net (code "93") (name "OSCK9") (class "Default")
      (node (ref "J49") (pin "16") (pinfunction "16_16") (pintype "passive"))
      (node (ref "J4A") (pin "7") (pinfunction "7_7") (pintype "passive"))
    )
    (net (code "94") (name "OSCK10") (class "Default")
      (node (ref "J4A") (pin "16") (pinfunction "16_16") (pintype "passive"))
      (node (ref "J4B") (pin "7") (pinfunction "7_7") (pintype "passive"))
    )
    (net (code "95") (name "OSCK11") (class "Default")
      (node (ref "J4B") (pin "16") (pinfunction "16_16") (pintype "passive"))
    )
    (net (code "96") (name "OSCK12") (class "Default")
      (node (ref "J4C") (pin "16") (pinfunction "16_16") (pintype "passive"))
      (node (ref "J4D") (pin "7") (pinfunction "7_7") (pintype "passive"))
    )
    (net (code "97") (name "OSCK13") (class "Default")
      (node (ref "J4D") (pin "16") (pinfunction "16_16") (pintype "passive"))
      (node (ref "J4E") (pin "7") (pinfunction "7_7") (pintype "passive"))
    )
    (net (code "98") (name "OSCK14") (class "Default")
      (node (ref "J4E") (pin "16") (pinfunction "16_16") (pintype "passive"))
      (node (ref "J4F") (pin "7") (pinfunction "7_7") (pintype "passive"))
    )
    (net (code "99") (name "OSCK15") (class "Default")
      (node (ref "J4F") (pin "16") (pinfunction "16_16") (pintype "passive"))
    )
    (net (code "100") (name "OUTMOSI_3V3") (class "Default")
      (node (ref "J03") (pin "15") (pinfunction "P15_15") (pintype "passive"))
      (node (ref "U01L") (pin "13") (pinfunction "13.B1_13") (pintype "passive"))
      (node (ref "U02L") (pin "13") (pinfunction "13.B1_13") (pintype "passive"))
      (node (ref "U03L") (pin "13") (pinfunction "13.B1_13") (pintype "passive"))
      (node (ref "U04L") (pin "13") (pinfunction "13.B1_13") (pintype "passive"))
    )
    (net (code "101") (name "VDD_1V8") (class "Default")
      (node (ref "C01D") (pin "1") (pinfunction "1_1") (pintype "passive"))
      (node (ref "C01O") (pin "1") (pinfunction "1_1") (pintype "passive"))
      (node (ref "C02O") (pin "1") (pinfunction "1_1") (pintype "passive"))
      (node (ref "C03D") (pin "1") (pinfunction "1_1") (pintype "passive"))
      (node (ref "C05D") (pin "1") (pinfunction "1_1") (pintype "passive"))
      (node (ref "C07D") (pin "1") (pinfunction "1_1") (pintype "passive"))
      (node (ref "J40") (pin "10") (pinfunction "10_10") (pintype "passive"))
      (node (ref "J40") (pin "20") (pinfunction "20_20") (pintype "passive"))
      (node (ref "J41") (pin "10") (pinfunction "10_10") (pintype "passive"))
      (node (ref "J41") (pin "20") (pinfunction "20_20") (pintype "passive"))
      (node (ref "J42") (pin "10") (pinfunction "10_10") (pintype "passive"))
      (node (ref "J42") (pin "20") (pinfunction "20_20") (pintype "passive"))
      (node (ref "J43") (pin "10") (pinfunction "10_10") (pintype "passive"))
      (node (ref "J43") (pin "20") (pinfunction "20_20") (pintype "passive"))
      (node (ref "J44") (pin "10") (pinfunction "10_10") (pintype "passive"))
      (node (ref "J44") (pin "20") (pinfunction "20_20") (pintype "passive"))
      (node (ref "J45") (pin "10") (pinfunction "10_10") (pintype "passive"))
      (node (ref "J45") (pin "20") (pinfunction "20_20") (pintype "passive"))
      (node (ref "J46") (pin "10") (pinfunction "10_10") (pintype "passive"))
      (node (ref "J46") (pin "20") (pinfunction "20_20") (pintype "passive"))
      (node (ref "J47") (pin "10") (pinfunction "10_10") (pintype "passive"))
      (node (ref "J47") (pin "20") (pinfunction "20_20") (pintype "passive"))
      (node (ref "J48") (pin "10") (pinfunction "10_10") (pintype "passive"))
      (node (ref "J48") (pin "20") (pinfunction "20_20") (pintype "passive"))
      (node (ref "J49") (pin "10") (pinfunction "10_10") (pintype "passive"))
      (node (ref "J49") (pin "20") (pinfunction "20_20") (pintype "passive"))
      (node (ref "J4A") (pin "10") (pinfunction "10_10") (pintype "passive"))
      (node (ref "J4A") (pin "20") (pinfunction "20_20") (pintype "passive"))
      (node (ref "J4B") (pin "10") (pinfunction "10_10") (pintype "passive"))
      (node (ref "J4B") (pin "20") (pinfunction "20_20") (pintype "passive"))
      (node (ref "J4C") (pin "10") (pinfunction "10_10") (pintype "passive"))
      (node (ref "J4C") (pin "20") (pinfunction "20_20") (pintype "passive"))
      (node (ref "J4D") (pin "10") (pinfunction "10_10") (pintype "passive"))
      (node (ref "J4D") (pin "20") (pinfunction "20_20") (pintype "passive"))
      (node (ref "J4E") (pin "10") (pinfunction "10_10") (pintype "passive"))
      (node (ref "J4E") (pin "20") (pinfunction "20_20") (pintype "passive"))
      (node (ref "J4F") (pin "10") (pinfunction "10_10") (pintype "passive"))
      (node (ref "J4F") (pin "20") (pinfunction "20_20") (pintype "passive"))
      (node (ref "L01") (pin "2") (pinfunction "2_2") (pintype "passive"))
      (node (ref "R01F") (pin "1") (pinfunction "1_1") (pintype "passive"))
      (node (ref "U01L") (pin "1") (pinfunction "1.VCCA_1") (pintype "passive"))
      (node (ref "U02L") (pin "1") (pinfunction "1.VCCA_1") (pintype "passive"))
      (node (ref "U03L") (pin "1") (pinfunction "1.VCCA_1") (pintype "passive"))
      (node (ref "U04L") (pin "1") (pinfunction "1.VCCA_1") (pintype "passive"))
    )
    (net (code "102") (name "VDD_3V3") (class "Default")
      (node (ref "C02D") (pin "1") (pinfunction "1_1") (pintype "passive"))
      (node (ref "C04D") (pin "1") (pinfunction "1_1") (pintype "passive"))
      (node (ref "C06D") (pin "1") (pinfunction "1_1") (pintype "passive"))
      (node (ref "C08D") (pin "1") (pinfunction "1_1") (pintype "passive"))
      (node (ref "J03") (pin "1") (pinfunction "P1_1") (pintype "passive"))
      (node (ref "U01L") (pin "14") (pinfunction "14.VDDB_14") (pintype "passive"))
      (node (ref "U02L") (pin "14") (pinfunction "14.VDDB_14") (pintype "passive"))
      (node (ref "U03L") (pin "14") (pinfunction "14.VDDB_14") (pintype "passive"))
      (node (ref "U04L") (pin "14") (pinfunction "14.VDDB_14") (pintype "passive"))
    )
    (net (code "103") (name "VDD_5V") (class "Default")
      (node (ref "C03O") (pin "1") (pinfunction "1_1") (pintype "passive"))
      (node (ref "C04O") (pin "1") (pinfunction "1_1") (pintype "passive"))
      (node (ref "J03") (pin "2") (pinfunction "P2_2") (pintype "passive"))
      (node (ref "J03") (pin "4") (pinfunction "P4_4") (pintype "passive"))
      (node (ref "L02") (pin "2") (pinfunction "2_2") (pintype "passive"))
      (node (ref "R03F") (pin "1") (pinfunction "1_1") (pintype "passive"))
    )
    (net (code "104") (name "VDD_POWER-IN") (class "Default")
      (node (ref "C01I") (pin "1") (pinfunction "1_1") (pintype "passive"))
      (node (ref "C02I") (pin "1") (pinfunction "1_1") (pintype "passive"))
      (node (ref "C03I") (pin "1") (pinfunction "1_1") (pintype "passive"))
      (node (ref "C04I") (pin "1") (pinfunction "1_1") (pintype "passive"))
      (node (ref "C05I") (pin "1") (pinfunction "1_1") (pintype "passive"))
      (node (ref "C06I") (pin "1") (pinfunction "1_1") (pintype "passive"))
      (node (ref "J01E") (pin "1") (pinfunction "1_1") (pintype "passive"))
      (node (ref "J01E") (pin "2") (pinfunction "2_2") (pintype "passive"))
      (node (ref "J01E") (pin "3") (pinfunction "3_3") (pintype "passive"))
      (node (ref "J01F") (pin "2") (pinfunction "2_2") (pintype "passive"))
      (node (ref "J01P") (pin "1") (pinfunction "1_1") (pintype "passive"))
      (node (ref "J01P") (pin "2") (pinfunction "2_2") (pintype "passive"))
      (node (ref "J01P") (pin "3") (pinfunction "3_3") (pintype "passive"))
      (node (ref "J01P") (pin "4") (pinfunction "4_4") (pintype "passive"))
      (node (ref "J01P") (pin "5") (pinfunction "5_5") (pintype "passive"))
      (node (ref "J01P") (pin "6") (pinfunction "6_6") (pintype "passive"))
      (node (ref "J02E") (pin "1") (pinfunction "1_1") (pintype "passive"))
      (node (ref "J02E") (pin "2") (pinfunction "2_2") (pintype "passive"))
      (node (ref "J02E") (pin "3") (pinfunction "3_3") (pintype "passive"))
      (node (ref "J02F") (pin "2") (pinfunction "2_2") (pintype "passive"))
      (node (ref "J03F") (pin "2") (pinfunction "2_2") (pintype "passive"))
      (node (ref "J40") (pin "1") (pinfunction "1_1") (pintype "passive"))
      (node (ref "J40") (pin "2") (pinfunction "2_2") (pintype "passive"))
      (node (ref "J40") (pin "3") (pinfunction "3_3") (pintype "passive"))
      (node (ref "J40") (pin "4") (pinfunction "4_4") (pintype "passive"))
      (node (ref "J41") (pin "1") (pinfunction "1_1") (pintype "passive"))
      (node (ref "J41") (pin "2") (pinfunction "2_2") (pintype "passive"))
      (node (ref "J41") (pin "3") (pinfunction "3_3") (pintype "passive"))
      (node (ref "J41") (pin "4") (pinfunction "4_4") (pintype "passive"))
      (node (ref "J42") (pin "1") (pinfunction "1_1") (pintype "passive"))
      (node (ref "J42") (pin "2") (pinfunction "2_2") (pintype "passive"))
      (node (ref "J42") (pin "3") (pinfunction "3_3") (pintype "passive"))
      (node (ref "J42") (pin "4") (pinfunction "4_4") (pintype "passive"))
      (node (ref "J43") (pin "1") (pinfunction "1_1") (pintype "passive"))
      (node (ref "J43") (pin "2") (pinfunction "2_2") (pintype "passive"))
      (node (ref "J43") (pin "3") (pinfunction "3_3") (pintype "passive"))
      (node (ref "J43") (pin "4") (pinfunction "4_4") (pintype "passive"))
      (node (ref "J44") (pin "1") (pinfunction "1_1") (pintype "passive"))
      (node (ref "J44") (pin "2") (pinfunction "2_2") (pintype "passive"))
      (node (ref "J44") (pin "3") (pinfunction "3_3") (pintype "passive"))
      (node (ref "J44") (pin "4") (pinfunction "4_4") (pintype "passive"))
      (node (ref "J45") (pin "1") (pinfunction "1_1") (pintype "passive"))
      (node (ref "J45") (pin "2") (pinfunction "2_2") (pintype "passive"))
      (node (ref "J45") (pin "3") (pinfunction "3_3") (pintype "passive"))
      (node (ref "J45") (pin "4") (pinfunction "4_4") (pintype "passive"))
      (node (ref "J46") (pin "1") (pinfunction "1_1") (pintype "passive"))
      (node (ref "J46") (pin "2") (pinfunction "2_2") (pintype "passive"))
      (node (ref "J46") (pin "3") (pinfunction "3_3") (pintype "passive"))
      (node (ref "J46") (pin "4") (pinfunction "4_4") (pintype "passive"))
      (node (ref "J47") (pin "1") (pinfunction "1_1") (pintype "passive"))
      (node (ref "J47") (pin "2") (pinfunction "2_2") (pintype "passive"))
      (node (ref "J47") (pin "3") (pinfunction "3_3") (pintype "passive"))
      (node (ref "J47") (pin "4") (pinfunction "4_4") (pintype "passive"))
      (node (ref "J48") (pin "1") (pinfunction "1_1") (pintype "passive"))
      (node (ref "J48") (pin "2") (pinfunction "2_2") (pintype "passive"))
      (node (ref "J48") (pin "3") (pinfunction "3_3") (pintype "passive"))
      (node (ref "J48") (pin "4") (pinfunction "4_4") (pintype "passive"))
      (node (ref "J49") (pin "1") (pinfunction "1_1") (pintype "passive"))
      (node (ref "J49") (pin "2") (pinfunction "2_2") (pintype "passive"))
      (node (ref "J49") (pin "3") (pinfunction "3_3") (pintype "passive"))
      (node (ref "J49") (pin "4") (pinfunction "4_4") (pintype "passive"))
      (node (ref "J4A") (pin "1") (pinfunction "1_1") (pintype "passive"))
      (node (ref "J4A") (pin "2") (pinfunction "2_2") (pintype "passive"))
      (node (ref "J4A") (pin "3") (pinfunction "3_3") (pintype "passive"))
      (node (ref "J4A") (pin "4") (pinfunction "4_4") (pintype "passive"))
      (node (ref "J4B") (pin "1") (pinfunction "1_1") (pintype "passive"))
      (node (ref "J4B") (pin "2") (pinfunction "2_2") (pintype "passive"))
      (node (ref "J4B") (pin "3") (pinfunction "3_3") (pintype "passive"))
      (node (ref "J4B") (pin "4") (pinfunction "4_4") (pintype "passive"))
      (node (ref "J4C") (pin "1") (pinfunction "1_1") (pintype "passive"))
      (node (ref "J4C") (pin "2") (pinfunction "2_2") (pintype "passive"))
      (node (ref "J4C") (pin "3") (pinfunction "3_3") (pintype "passive"))
      (node (ref "J4C") (pin "4") (pinfunction "4_4") (pintype "passive"))
      (node (ref "J4D") (pin "1") (pinfunction "1_1") (pintype "passive"))
      (node (ref "J4D") (pin "2") (pinfunction "2_2") (pintype "passive"))
      (node (ref "J4D") (pin "3") (pinfunction "3_3") (pintype "passive"))
      (node (ref "J4D") (pin "4") (pinfunction "4_4") (pintype "passive"))
      (node (ref "J4E") (pin "1") (pinfunction "1_1") (pintype "passive"))
      (node (ref "J4E") (pin "2") (pinfunction "2_2") (pintype "passive"))
      (node (ref "J4E") (pin "3") (pinfunction "3_3") (pintype "passive"))
      (node (ref "J4E") (pin "4") (pinfunction "4_4") (pintype "passive"))
      (node (ref "J4F") (pin "1") (pinfunction "1_1") (pintype "passive"))
      (node (ref "J4F") (pin "2") (pinfunction "2_2") (pintype "passive"))
      (node (ref "J4F") (pin "3") (pinfunction "3_3") (pintype "passive"))
      (node (ref "J4F") (pin "4") (pinfunction "4_4") (pintype "passive"))
      (node (ref "R01E") (pin "1") (pinfunction "1_1") (pintype "passive"))
      (node (ref "R02E") (pin "1") (pinfunction "1_1") (pintype "passive"))
      (node (ref "U01") (pin "1") (pinfunction "1.VIN1_1") (pintype "passive"))
      (node (ref "U01") (pin "16") (pinfunction "16.VIN2_16") (pintype "passive"))
    )
    (net (code "105") (name "unconnected-(J01F-Pad1)") (class "Default")
      (node (ref "J01F") (pin "1") (pinfunction "1_1") (pintype "passive"))
    )
    (net (code "106") (name "unconnected-(J02F-Pad1)") (class "Default")
      (node (ref "J02F") (pin "1") (pinfunction "1_1") (pintype "passive"))
    )
    (net (code "107") (name "unconnected-(J03-P3-Pad3)") (class "Default")
      (node (ref "J03") (pin "3") (pinfunction "P3_3") (pintype "passive"))
    )
    (net (code "108") (name "unconnected-(J03-P5-Pad5)") (class "Default")
      (node (ref "J03") (pin "5") (pinfunction "P5_5") (pintype "passive"))
    )
    (net (code "109") (name "unconnected-(J03-P7-Pad7)") (class "Default")
      (node (ref "J03") (pin "7") (pinfunction "P7_7") (pintype "passive"))
    )
    (net (code "110") (name "unconnected-(J03-P8-Pad8)") (class "Default")
      (node (ref "J03") (pin "8") (pinfunction "P8_8") (pintype "passive"))
    )
    (net (code "111") (name "unconnected-(J03-P10-Pad10)") (class "Default")
      (node (ref "J03") (pin "10") (pinfunction "P10_10") (pintype "passive"))
    )
    (net (code "112") (name "unconnected-(J03-P11-Pad11)") (class "Default")
      (node (ref "J03") (pin "11") (pinfunction "P11_11") (pintype "passive"))
    )
    (net (code "113") (name "unconnected-(J03-P13-Pad13)") (class "Default")
      (node (ref "J03") (pin "13") (pinfunction "P13_13") (pintype "passive"))
    )
    (net (code "114") (name "unconnected-(J03-P17-Pad17)") (class "Default")
      (node (ref "J03") (pin "17") (pinfunction "P17_17") (pintype "passive"))
    )
    (net (code "115") (name "unconnected-(J03-P24-Pad24)") (class "Default")
      (node (ref "J03") (pin "24") (pinfunction "P24_24") (pintype "passive"))
    )
    (net (code "116") (name "unconnected-(J03-P26-Pad26)") (class "Default")
      (node (ref "J03") (pin "26") (pinfunction "P26_26") (pintype "passive"))
    )
    (net (code "117") (name "unconnected-(J03F-Pad1)") (class "Default")
      (node (ref "J03F") (pin "1") (pinfunction "1_1") (pintype "passive"))
    )
    (net (code "118") (name "unconnected-(J4A-Pad19)") (class "Default")
      (node (ref "J4A") (pin "19") (pinfunction "19_19") (pintype "passive"))
    )
    (net (code "119") (name "unconnected-(J4B-Pad19)") (class "Default")
      (node (ref "J4B") (pin "19") (pinfunction "19_19") (pintype "passive"))
    )
    (net (code "120") (name "unconnected-(J4C-Pad19)") (class "Default")
      (node (ref "J4C") (pin "19") (pinfunction "19_19") (pintype "passive"))
    )
    (net (code "121") (name "unconnected-(J4D-Pad19)") (class "Default")
      (node (ref "J4D") (pin "19") (pinfunction "19_19") (pintype "passive"))
    )
    (net (code "122") (name "unconnected-(J4E-Pad19)") (class "Default")
      (node (ref "J4E") (pin "19") (pinfunction "19_19") (pintype "passive"))
    )
    (net (code "123") (name "unconnected-(J4F-Pad19)") (class "Default")
      (node (ref "J4F") (pin "19") (pinfunction "19_19") (pintype "passive"))
    )
    (net (code "124") (name "unconnected-(J40-Pad19)") (class "Default")
      (node (ref "J40") (pin "19") (pinfunction "19_19") (pintype "passive"))
    )
    (net (code "125") (name "unconnected-(J41-Pad19)") (class "Default")
      (node (ref "J41") (pin "19") (pinfunction "19_19") (pintype "passive"))
    )
    (net (code "126") (name "unconnected-(J42-Pad19)") (class "Default")
      (node (ref "J42") (pin "19") (pinfunction "19_19") (pintype "passive"))
    )
    (net (code "127") (name "unconnected-(J43-Pad19)") (class "Default")
      (node (ref "J43") (pin "19") (pinfunction "19_19") (pintype "passive"))
    )
    (net (code "128") (name "unconnected-(J44-Pad19)") (class "Default")
      (node (ref "J44") (pin "19") (pinfunction "19_19") (pintype "passive"))
    )
    (net (code "129") (name "unconnected-(J45-Pad19)") (class "Default")
      (node (ref "J45") (pin "19") (pinfunction "19_19") (pintype "passive"))
    )
    (net (code "130") (name "unconnected-(J46-Pad19)") (class "Default")
      (node (ref "J46") (pin "19") (pinfunction "19_19") (pintype "passive"))
    )
    (net (code "131") (name "unconnected-(J47-Pad19)") (class "Default")
      (node (ref "J47") (pin "19") (pinfunction "19_19") (pintype "passive"))
    )
    (net (code "132") (name "unconnected-(J48-Pad19)") (class "Default")
      (node (ref "J48") (pin "19") (pinfunction "19_19") (pintype "passive"))
    )
    (net (code "133") (name "unconnected-(J49-Pad19)") (class "Default")
      (node (ref "J49") (pin "19") (pinfunction "19_19") (pintype "passive"))
    )
    (net (code "134") (name "unconnected-(U01L-6.NC-Pad6)") (class "Default")
      (node (ref "U01L") (pin "6") (pinfunction "6.NC_6") (pintype "passive"))
    )
    (net (code "135") (name "unconnected-(U01L-9.NC-Pad9)") (class "Default")
      (node (ref "U01L") (pin "9") (pinfunction "9.NC_9") (pintype "passive"))
    )
    (net (code "136") (name "unconnected-(U02L-6.NC-Pad6)") (class "Default")
      (node (ref "U02L") (pin "6") (pinfunction "6.NC_6") (pintype "passive"))
    )
    (net (code "137") (name "unconnected-(U02L-9.NC-Pad9)") (class "Default")
      (node (ref "U02L") (pin "9") (pinfunction "9.NC_9") (pintype "passive"))
    )
    (net (code "138") (name "unconnected-(U03L-6.NC-Pad6)") (class "Default")
      (node (ref "U03L") (pin "6") (pinfunction "6.NC_6") (pintype "passive"))
    )
    (net (code "139") (name "unconnected-(U03L-9.NC-Pad9)") (class "Default")
      (node (ref "U03L") (pin "9") (pinfunction "9.NC_9") (pintype "passive"))
    )
    (net (code "140") (name "unconnected-(U04L-6.NC-Pad6)") (class "Default")
      (node (ref "U04L") (pin "6") (pinfunction "6.NC_6") (pintype "passive"))
    )
    (net (code "141") (name "unconnected-(U04L-9.NC-Pad9)") (class "Default")
      (node (ref "U04L") (pin "9") (pinfunction "9.NC_9") (pintype "passive"))
    )
  )
)
